# samotneesp.net
KiCad netlist of a schematic drawn in EAGLE
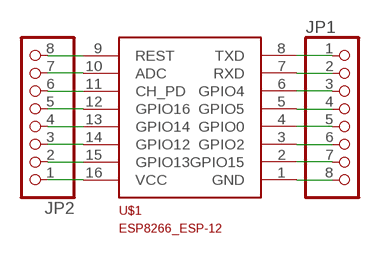
[diagram p0: schematic, sheet 1]

(export (version "E")
  (design (tool "Eeschema 10.0.6"))
  (components
    (comp (ref "JP1")
      (value "PINHD-1X8")
      (footprint "eagle-import:1X08")
      (libsource (lib "eagle-import") (part "PINHD-1X8"))
    )
    (comp (ref "JP2")
      (value "PINHD-1X8")
      (footprint "eagle-import:1X08")
      (libsource (lib "eagle-import") (part "PINHD-1X8"))
    )
    (comp (ref "U$1")
      (value "ESP8266_ESP-12")
      (footprint "eagle-import:ESP8266-ESP12")
      (libsource (lib "eagle-import") (part "ESP8266_ESP-12"))
    )
  )
  (nets
    (net (code "1") (name "Net-(U$1-ADC)") (class "Default")
      (node (ref "JP2") (pin "7") (pinfunction "7_7") (pintype "passive"))
      (node (ref "U$1") (pin "10") (pinfunction "ADC_10") (pintype "bidirectional"))
    )
    (net (code "2") (name "Net-(U$1-CH_PD)") (class "Default")
      (node (ref "JP2") (pin "6") (pinfunction "6_6") (pintype "passive"))
      (node (ref "U$1") (pin "11") (pinfunction "CH_PD_11") (pintype "bidirectional"))
    )
    (net (code "3") (name "Net-(U$1-GND)") (class "Default")
      (node (ref "JP1") (pin "8") (pinfunction "8_8") (pintype "passive"))
      (node (ref "U$1") (pin "1") (pinfunction "GND_1") (pintype "bidirectional"))
    )
    (net (code "4") (name "Net-(U$1-GPIO0)") (class "Default")
      (node (ref "JP1") (pin "5") (pinfunction "5_5") (pintype "passive"))
      (node (ref "U$1") (pin "4") (pinfunction "GPIO0_4") (pintype "bidirectional"))
    )
    (net (code "5") (name "Net-(U$1-GPIO2)") (class "Default")
      (node (ref "JP1") (pin "6") (pinfunction "6_6") (pintype "passive"))
      (node (ref "U$1") (pin "3") (pinfunction "GPIO2_3") (pintype "bidirectional"))
    )
    (net (code "6") (name "Net-(U$1-GPIO4)") (class "Default")
      (node (ref "JP1") (pin "3") (pinfunction "3_3") (pintype "passive"))
      (node (ref "U$1") (pin "6") (pinfunction "GPIO4_6") (pintype "bidirectional"))
    )
    (net (code "7") (name "Net-(U$1-GPIO5)") (class "Default")
      (node (ref "JP1") (pin "4") (pinfunction "4_4") (pintype "passive"))
      (node (ref "U$1") (pin "5") (pinfunction "GPIO5_5") (pintype "bidirectional"))
    )
    (net (code "8") (name "Net-(U$1-GPIO12)") (class "Default")
      (node (ref "JP2") (pin "3") (pinfunction "3_3") (pintype "passive"))
      (node (ref "U$1") (pin "14") (pinfunction "GPIO12_14") (pintype "bidirectional"))
    )
    (net (code "9") (name "Net-(U$1-GPIO13)") (class "Default")
      (node (ref "JP2") (pin "2") (pinfunction "2_2") (pintype "passive"))
      (node (ref "U$1") (pin "15") (pinfunction "GPIO13_15") (pintype "bidirectional"))
    )
    (net (code "10") (name "Net-(U$1-GPIO14)") (class "Default")
      (node (ref "JP2") (pin "4") (pinfunction "4_4") (pintype "passive"))
      (node (ref "U$1") (pin "13") (pinfunction "GPIO14_13") (pintype "bidirectional"))
    )
    (net (code "11") (name "Net-(U$1-GPIO15)") (class "Default")
      (node (ref "JP1") (pin "7") (pinfunction "7_7") (pintype "passive"))
      (node (ref "U$1") (pin "2") (pinfunction "GPIO15_2") (pintype "bidirectional"))
    )
    (net (code "12") (name "Net-(U$1-GPIO16)") (class "Default")
      (node (ref "JP2") (pin "5") (pinfunction "5_5") (pintype "passive"))
      (node (ref "U$1") (pin "12") (pinfunction "GPIO16_12") (pintype "bidirectional"))
    )
    (net (code "13") (name "Net-(U$1-REST)") (class "Default")
      (node (ref "JP2") (pin "8") (pinfunction "8_8") (pintype "passive"))
      (node (ref "U$1") (pin "9") (pinfunction "REST_9") (pintype "bidirectional"))
    )
    (net (code "14") (name "Net-(U$1-RXD)") (class "Default")
      (node (ref "JP1") (pin "2") (pinfunction "2_2") (pintype "passive"))
      (node (ref "U$1") (pin "7") (pinfunction "RXD_7") (pintype "bidirectional"))
    )
    (net (code "15") (name "Net-(U$1-TXD)") (class "Default")
      (node (ref "JP1") (pin "1") (pinfunction "1_1") (pintype "passive"))
      (node (ref "U$1") (pin "8") (pinfunction "TXD_8") (pintype "bidirectional"))
    )
    (net (code "16") (name "Net-(U$1-VCC)") (class "Default")
      (node (ref "JP2") (pin "1") (pinfunction "1_1") (pintype "passive"))
      (node (ref "U$1") (pin "16") (pinfunction "VCC_16") (pintype "bidirectional"))
    )
  )
)
